# Bending_Machine_SCH.net
KiCad netlist of a schematic drawn in Altium Designer
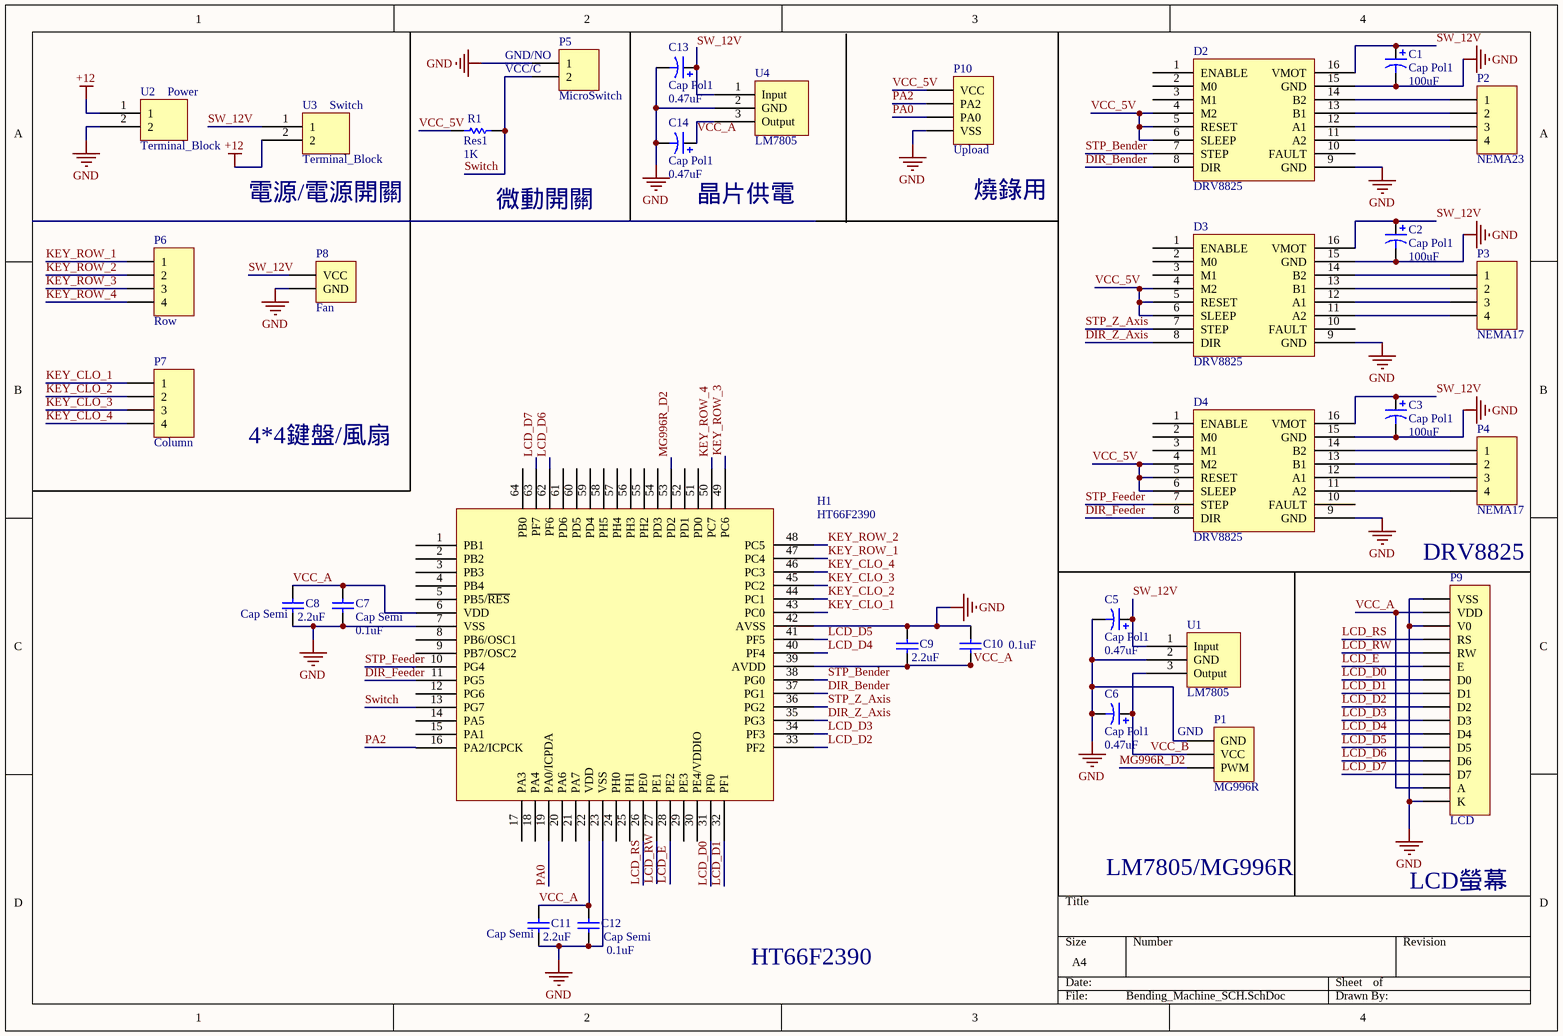
[diagram p0: Bending_Machine_SCH.SchDoc]

(export (version "E")
  (design (tool "Eeschema 10.0.6"))
  (components
    (comp (ref "C1")
      (value "Cap Pol1")
      (footprint "Cap_100uF")
      (description "Polarized Capacitor (Radial)")
      (fields (field (name "ALTIUM_VALUE") "100uF") (field (name "PUBLISHER") "Altium Limited"))
      (libsource (lib "Miscellaneous Devices") (part "Cap Pol1"))
    )
    (comp (ref "C2")
      (value "Cap Pol1")
      (footprint "Cap_100uF")
      (description "Polarized Capacitor (Radial)")
      (fields (field (name "ALTIUM_VALUE") "100uF") (field (name "PUBLISHER") "Altium Limited"))
      (libsource (lib "Miscellaneous Devices") (part "Cap Pol1"))
    )
    (comp (ref "C3")
      (value "Cap Pol1")
      (footprint "Cap_100uF")
      (description "Polarized Capacitor (Radial)")
      (fields (field (name "ALTIUM_VALUE") "100uF") (field (name "PUBLISHER") "Altium Limited"))
      (libsource (lib "Miscellaneous Devices") (part "Cap Pol1"))
    )
    (comp (ref "C5")
      (value "Cap Pol1")
      (footprint "Cap_0.47uF")
      (description "Polarized Capacitor (Radial)")
      (fields (field (name "ALTIUM_VALUE") "0.47uF") (field (name "PUBLISHER") "Altium Limited"))
      (libsource (lib "Miscellaneous Devices") (part "Cap Pol1"))
    )
    (comp (ref "C6")
      (value "Cap Pol1")
      (footprint "Cap_0.47uF")
      (description "Polarized Capacitor (Radial)")
      (fields (field (name "ALTIUM_VALUE") "0.47uF") (field (name "PUBLISHER") "Altium Limited"))
      (libsource (lib "Miscellaneous Devices") (part "Cap Pol1"))
    )
    (comp (ref "C7")
      (value "Cap Semi")
      (footprint "1608[0603]")
      (description "Capacitor (Semiconductor SIM Model)")
      (fields (field (name "ALTIUM_VALUE") "0.1uF") (field (name "PUBLISHER") "Altium Limited"))
      (libsource (lib "Miscellaneous Devices") (part "Cap Semi"))
    )
    (comp (ref "C8")
      (value "Cap Semi")
      (footprint "1608[0603]")
      (description "Capacitor (Semiconductor SIM Model)")
      (fields (field (name "ALTIUM_VALUE") "2.2uF") (field (name "PUBLISHER") "Altium Limited"))
      (libsource (lib "Miscellaneous Devices") (part "Cap Semi"))
    )
    (comp (ref "C9")
      (value "2.2uF")
      (footprint "1608[0603]")
      (description "Capacitor (Semiconductor SIM Model)")
      (fields (field (name "Comment") "Cap Semi") (field (name "PUBLISHER") "Altium Limited"))
      (libsource (lib "Miscellaneous Devices") (part "Cap Semi"))
    )
    (comp (ref "C10")
      (value "0.1uF")
      (footprint "1608[0603]")
      (description "Capacitor (Semiconductor SIM Model)")
      (fields (field (name "Comment") "Cap Semi") (field (name "PUBLISHER") "Altium Limited"))
      (libsource (lib "Miscellaneous Devices") (part "Cap Semi"))
    )
    (comp (ref "C11")
      (value "Cap Semi")
      (footprint "1608[0603]")
      (description "Capacitor (Semiconductor SIM Model)")
      (fields (field (name "ALTIUM_VALUE") "2.2uF") (field (name "PUBLISHER") "Altium Limited"))
      (libsource (lib "Miscellaneous Devices") (part "Cap Semi"))
    )
    (comp (ref "C12")
      (value "Cap Semi")
      (footprint "1608[0603]")
      (description "Capacitor (Semiconductor SIM Model)")
      (fields (field (name "ALTIUM_VALUE") "0.1uF") (field (name "PUBLISHER") "Altium Limited"))
      (libsource (lib "Miscellaneous Devices") (part "Cap Semi"))
    )
    (comp (ref "C13")
      (value "Cap Pol1")
      (footprint "Cap_0.47uF")
      (description "Polarized Capacitor (Radial)")
      (fields (field (name "ALTIUM_VALUE") "0.47uF") (field (name "PUBLISHER") "Altium Limited"))
      (libsource (lib "Miscellaneous Devices") (part "Cap Pol1"))
    )
    (comp (ref "C14")
      (value "Cap Pol1")
      (footprint "Cap_0.47uF")
      (description "Polarized Capacitor (Radial)")
      (fields (field (name "ALTIUM_VALUE") "0.47uF") (field (name "PUBLISHER") "Altium Limited"))
      (libsource (lib "Miscellaneous Devices") (part "Cap Pol1"))
    )
    (comp (ref "D2")
      (value "DRV8825")
      (footprint "DRV8825")
      (libsource (lib "Bending_Machine") (part "DRV8825"))
    )
    (comp (ref "D3")
      (value "DRV8825")
      (footprint "DRV8825")
      (libsource (lib "Bending_Machine") (part "DRV8825"))
    )
    (comp (ref "D4")
      (value "DRV8825")
      (footprint "DRV8825")
      (libsource (lib "Bending_Machine") (part "DRV8825"))
    )
    (comp (ref "H1")
      (value "HT66F2390")
      (footprint "HT66F2390_Bord")
      (libsource (lib "Bending_Machine") (part "HT66F2390"))
    )
    (comp (ref "P1")
      (value "MG996R")
      (footprint "HDR1X3")
      (description "Header, 3-Pin")
      (fields (field (name "PUBLISHER") "Altium Limited"))
      (libsource (lib "Miscellaneous Connectors") (part "Header 3"))
    )
    (comp (ref "P2")
      (value "NEMA23")
      (footprint "HDR1X4")
      (description "Header, 4-Pin")
      (fields (field (name "PUBLISHER") "Altium Limited"))
      (libsource (lib "Miscellaneous Connectors") (part "Header 4"))
    )
    (comp (ref "P3")
      (value "NEMA17")
      (footprint "HDR1X4")
      (description "Header, 4-Pin")
      (fields (field (name "PUBLISHER") "Altium Limited"))
      (libsource (lib "Miscellaneous Connectors") (part "Header 4"))
    )
    (comp (ref "P4")
      (value "NEMA17")
      (footprint "HDR1X4")
      (description "Header, 4-Pin")
      (fields (field (name "PUBLISHER") "Altium Limited"))
      (libsource (lib "Miscellaneous Connectors") (part "Header 4"))
    )
    (comp (ref "P5")
      (value "MicroSwitch")
      (footprint "HDR1X2")
      (description "Header, 2-Pin")
      (fields (field (name "PUBLISHER") "Altium Limited"))
      (libsource (lib "Miscellaneous Connectors") (part "Header 2"))
    )
    (comp (ref "P6")
      (value "Row")
      (footprint "HDR1X4")
      (description "Header, 4-Pin")
      (fields (field (name "PUBLISHER") "Altium Limited"))
      (libsource (lib "Miscellaneous Connectors") (part "Header 4"))
    )
    (comp (ref "P7")
      (value "Column")
      (footprint "HDR1X4")
      (description "Header, 4-Pin")
      (fields (field (name "PUBLISHER") "Altium Limited"))
      (libsource (lib "Miscellaneous Connectors") (part "Header 4"))
    )
    (comp (ref "P8")
      (value "Fan")
      (footprint "HDR1X2")
      (description "Header, 2-Pin")
      (fields (field (name "PUBLISHER") "Altium Limited"))
      (libsource (lib "Miscellaneous Connectors") (part "Header 2"))
    )
    (comp (ref "P9")
      (value "LCD")
      (footprint "HDR1X16")
      (description "Header, 16-Pin")
      (fields (field (name "PUBLISHER") "Altium Limited"))
      (libsource (lib "Miscellaneous Connectors") (part "Header 16"))
    )
    (comp (ref "P10")
      (value "Upload")
      (footprint "HDR1X4")
      (description "Header, 4-Pin")
      (fields (field (name "PUBLISHER") "Altium Limited"))
      (libsource (lib "Miscellaneous Connectors") (part "Header 4"))
    )
    (comp (ref "R1")
      (value "Res1")
      (footprint "AXIAL-0.3")
      (description "Resistor")
      (fields (field (name "ALTIUM_VALUE") "1K") (field (name "PUBLISHER") "Altium Limited"))
      (libsource (lib "Miscellaneous Devices") (part "Res1"))
    )
    (comp (ref "U1")
      (value "LM7805")
      (footprint "LM7805")
      (libsource (lib "Bending_Machine") (part "LM7805"))
    )
    (comp (ref "U2")
      (value "Terminal_Block")
      (footprint "terminal block")
      (libsource (lib "Bending_Machine") (part "Terminal Block"))
    )
    (comp (ref "U3")
      (value "Terminal_Block")
      (footprint "terminal block")
      (libsource (lib "Bending_Machine") (part "Terminal Block"))
    )
    (comp (ref "U4")
      (value "LM7805")
      (footprint "LM7805")
      (libsource (lib "Bending_Machine") (part "LM7805"))
    )
  )
  (nets
    (net (code "1") (name "+12") (class "Default")
      (node (ref "U2") (pin "1") (pinfunction "1_1") (pintype "passive"))
      (node (ref "U3") (pin "2") (pinfunction "2_2") (pintype "passive"))
    )
    (net (code "3") (name "/DIR_Bender") (class "Default")
      (node (ref "D2") (pin "8") (pinfunction "DIR_8") (pintype "passive"))
      (node (ref "H1") (pin "37") (pinfunction "PG1_37") (pintype "passive"))
    )
    (net (code "4") (name "/DIR_Feeder") (class "Default")
      (node (ref "D4") (pin "8") (pinfunction "DIR_8") (pintype "passive"))
      (node (ref "H1") (pin "11") (pinfunction "PG5_11") (pintype "passive"))
    )
    (net (code "5") (name "/DIR_Z_Axis") (class "Default")
      (node (ref "D3") (pin "8") (pinfunction "DIR_8") (pintype "passive"))
      (node (ref "H1") (pin "35") (pinfunction "PG3_35") (pintype "passive"))
    )
    (net (code "6") (name "/KEY_CLO_1") (class "Default")
      (node (ref "H1") (pin "43") (pinfunction "PC0_43") (pintype "passive"))
      (node (ref "P7") (pin "1") (pinfunction "1_1") (pintype "passive"))
    )
    (net (code "7") (name "/KEY_CLO_2") (class "Default")
      (node (ref "H1") (pin "44") (pinfunction "PC1_44") (pintype "passive"))
      (node (ref "P7") (pin "2") (pinfunction "2_2") (pintype "passive"))
    )
    (net (code "8") (name "/KEY_CLO_3") (class "Default")
      (node (ref "H1") (pin "45") (pinfunction "PC2_45") (pintype "passive"))
      (node (ref "P7") (pin "3") (pinfunction "3_3") (pintype "passive"))
    )
    (net (code "9") (name "/KEY_CLO_4") (class "Default")
      (node (ref "H1") (pin "46") (pinfunction "PC3_46") (pintype "passive"))
      (node (ref "P7") (pin "4") (pinfunction "4_4") (pintype "passive"))
    )
    (net (code "10") (name "/KEY_ROW_1") (class "Default")
      (node (ref "H1") (pin "47") (pinfunction "PC4_47") (pintype "passive"))
      (node (ref "P6") (pin "1") (pinfunction "1_1") (pintype "passive"))
    )
    (net (code "11") (name "/KEY_ROW_2") (class "Default")
      (node (ref "H1") (pin "48") (pinfunction "PC5_48") (pintype "passive"))
      (node (ref "P6") (pin "2") (pinfunction "2_2") (pintype "passive"))
    )
    (net (code "12") (name "/KEY_ROW_3") (class "Default")
      (node (ref "H1") (pin "49") (pinfunction "PC6_49") (pintype "passive"))
      (node (ref "P6") (pin "3") (pinfunction "3_3") (pintype "passive"))
    )
    (net (code "13") (name "/KEY_ROW_4") (class "Default")
      (node (ref "H1") (pin "50") (pinfunction "PC7_50") (pintype "passive"))
      (node (ref "P6") (pin "4") (pinfunction "4_4") (pintype "passive"))
    )
    (net (code "14") (name "/LCD_D0") (class "Default")
      (node (ref "H1") (pin "31") (pinfunction "PF0_31") (pintype "passive"))
      (node (ref "P9") (pin "7") (pinfunction "D0_7") (pintype "passive"))
    )
    (net (code "15") (name "/LCD_D1") (class "Default")
      (node (ref "H1") (pin "32") (pinfunction "PF1_32") (pintype "passive"))
      (node (ref "P9") (pin "8") (pinfunction "D1_8") (pintype "passive"))
    )
    (net (code "16") (name "/LCD_D2") (class "Default")
      (node (ref "H1") (pin "33") (pinfunction "PF2_33") (pintype "passive"))
      (node (ref "P9") (pin "9") (pinfunction "D2_9") (pintype "passive"))
    )
    (net (code "17") (name "/LCD_D3") (class "Default")
      (node (ref "H1") (pin "34") (pinfunction "PF3_34") (pintype "passive"))
      (node (ref "P9") (pin "10") (pinfunction "D3_10") (pintype "passive"))
    )
    (net (code "18") (name "/LCD_D4") (class "Default")
      (node (ref "H1") (pin "40") (pinfunction "PF4_40") (pintype "passive"))
      (node (ref "P9") (pin "11") (pinfunction "D4_11") (pintype "passive"))
    )
    (net (code "19") (name "/LCD_D5") (class "Default")
      (node (ref "H1") (pin "41") (pinfunction "PF5_41") (pintype "passive"))
      (node (ref "P9") (pin "12") (pinfunction "D5_12") (pintype "passive"))
    )
    (net (code "20") (name "/LCD_D6") (class "Default")
      (node (ref "H1") (pin "62") (pinfunction "PF6_62") (pintype "passive"))
      (node (ref "P9") (pin "13") (pinfunction "D6_13") (pintype "passive"))
    )
    (net (code "21") (name "/LCD_D7") (class "Default")
      (node (ref "H1") (pin "63") (pinfunction "PF7_63") (pintype "passive"))
      (node (ref "P9") (pin "14") (pinfunction "D7_14") (pintype "passive"))
    )
    (net (code "22") (name "/LCD_E") (class "Default")
      (node (ref "H1") (pin "28") (pinfunction "PE2_28") (pintype "passive"))
      (node (ref "P9") (pin "6") (pinfunction "E_6") (pintype "passive"))
    )
    (net (code "23") (name "/LCD_RS") (class "Default")
      (node (ref "H1") (pin "26") (pinfunction "PE0_26") (pintype "passive"))
      (node (ref "P9") (pin "4") (pinfunction "RS_4") (pintype "passive"))
    )
    (net (code "24") (name "/LCD_RW") (class "Default")
      (node (ref "H1") (pin "27") (pinfunction "PE1_27") (pintype "passive"))
      (node (ref "P9") (pin "5") (pinfunction "RW_5") (pintype "passive"))
    )
    (net (code "25") (name "/MG996R_D2") (class "Default")
      (node (ref "H1") (pin "53") (pinfunction "PD2_53") (pintype "passive"))
      (node (ref "P1") (pin "3") (pinfunction "PWM_3") (pintype "passive"))
    )
    (net (code "26") (name "/PA0") (class "Default")
      (node (ref "H1") (pin "19") (pinfunction "PA0/ICPDA_19") (pintype "passive"))
      (node (ref "P10") (pin "3") (pinfunction "3_3") (pintype "passive"))
    )
    (net (code "27") (name "/PA2") (class "Default")
      (node (ref "H1") (pin "16") (pinfunction "PA2/ICPCK_16") (pintype "passive"))
      (node (ref "P10") (pin "2") (pinfunction "2_2") (pintype "passive"))
    )
    (net (code "28") (name "/STP_Bender") (class "Default")
      (node (ref "D2") (pin "7") (pinfunction "STEP_7") (pintype "passive"))
      (node (ref "H1") (pin "38") (pinfunction "PG0_38") (pintype "passive"))
    )
    (net (code "29") (name "/STP_Feeder") (class "Default")
      (node (ref "D4") (pin "7") (pinfunction "STEP_7") (pintype "passive"))
      (node (ref "H1") (pin "10") (pinfunction "PG4_10") (pintype "passive"))
    )
    (net (code "30") (name "/STP_Z_Axis") (class "Default")
      (node (ref "D3") (pin "7") (pinfunction "STEP_7") (pintype "passive"))
      (node (ref "H1") (pin "36") (pinfunction "PG2_36") (pintype "passive"))
    )
    (net (code "31") (name "/SW_12V") (class "Default")
      (node (ref "C1") (pin "1") (pinfunction "1_1") (pintype "passive"))
      (node (ref "C13") (pin "1") (pinfunction "1_1") (pintype "passive"))
      (node (ref "C2") (pin "1") (pinfunction "1_1") (pintype "passive"))
      (node (ref "C3") (pin "1") (pinfunction "1_1") (pintype "passive"))
      (node (ref "C5") (pin "1") (pinfunction "1_1") (pintype "passive"))
      (node (ref "D2") (pin "16") (pinfunction "VMOT_16") (pintype "passive"))
      (node (ref "D3") (pin "16") (pinfunction "VMOT_16") (pintype "passive"))
      (node (ref "D4") (pin "16") (pinfunction "VMOT_16") (pintype "passive"))
      (node (ref "P8") (pin "1") (pinfunction "1_1") (pintype "passive"))
      (node (ref "U1") (pin "1") (pinfunction "Input_1") (pintype "passive"))
      (node (ref "U3") (pin "1") (pinfunction "1_1") (pintype "passive"))
      (node (ref "U4") (pin "1") (pinfunction "Input_1") (pintype "passive"))
    )
    (net (code "32") (name "/Switch") (class "Default")
      (node (ref "H1") (pin "13") (pinfunction "PG7_13") (pintype "passive"))
      (node (ref "P5") (pin "2") (pinfunction "2_2") (pintype "passive"))
      (node (ref "R1") (pin "2") (pinfunction "2_2") (pintype "passive"))
    )
    (net (code "33") (name "/VCC_5V") (class "Default")
      (node (ref "D2") (pin "4") (pinfunction "M2_4") (pintype "passive"))
      (node (ref "D2") (pin "5") (pinfunction "RESET_5") (pintype "passive"))
      (node (ref "D2") (pin "6") (pinfunction "SLEEP_6") (pintype "passive"))
      (node (ref "D3") (pin "4") (pinfunction "M2_4") (pintype "passive"))
      (node (ref "D3") (pin "5") (pinfunction "RESET_5") (pintype "passive"))
      (node (ref "D3") (pin "6") (pinfunction "SLEEP_6") (pintype "passive"))
      (node (ref "D4") (pin "4") (pinfunction "M2_4") (pintype "passive"))
      (node (ref "D4") (pin "5") (pinfunction "RESET_5") (pintype "passive"))
      (node (ref "D4") (pin "6") (pinfunction "SLEEP_6") (pintype "passive"))
      (node (ref "P10") (pin "1") (pinfunction "1_1") (pintype "passive"))
      (node (ref "R1") (pin "1") (pinfunction "1_1") (pintype "passive"))
    )
    (net (code "34") (name "/VCC_A") (class "Default")
      (node (ref "C10") (pin "1") (pinfunction "1_1") (pintype "passive"))
      (node (ref "C11") (pin "2") (pinfunction "2_2") (pintype "passive"))
      (node (ref "C12") (pin "2") (pinfunction "2_2") (pintype "passive"))
      (node (ref "C14") (pin "1") (pinfunction "1_1") (pintype "passive"))
      (node (ref "C7") (pin "2") (pinfunction "2_2") (pintype "passive"))
      (node (ref "C8") (pin "2") (pinfunction "2_2") (pintype "passive"))
      (node (ref "C9") (pin "1") (pinfunction "1_1") (pintype "passive"))
      (node (ref "H1") (pin "22") (pinfunction "VDD_22") (pintype "passive"))
      (node (ref "H1") (pin "39") (pinfunction "AVDD_39") (pintype "passive"))
      (node (ref "H1") (pin "6") (pinfunction "VDD_6") (pintype "passive"))
      (node (ref "P9") (pin "15") (pinfunction "A_15") (pintype "passive"))
      (node (ref "P9") (pin "2") (pinfunction "VDD_2") (pintype "passive"))
      (node (ref "U4") (pin "3") (pinfunction "Output_3") (pintype "passive"))
    )
    (net (code "35") (name "/VCC_B") (class "Default")
      (node (ref "C6") (pin "1") (pinfunction "1_1") (pintype "passive"))
      (node (ref "P1") (pin "2") (pinfunction "VCC_2") (pintype "passive"))
      (node (ref "U1") (pin "3") (pinfunction "Output_3") (pintype "passive"))
    )
    (net (code "36") (name "GND") (class "Default")
      (node (ref "C1") (pin "2") (pinfunction "2_2") (pintype "passive"))
      (node (ref "C10") (pin "2") (pinfunction "2_2") (pintype "passive"))
      (node (ref "C11") (pin "1") (pinfunction "1_1") (pintype "passive"))
      (node (ref "C12") (pin "1") (pinfunction "1_1") (pintype "passive"))
      (node (ref "C13") (pin "2") (pinfunction "2_2") (pintype "passive"))
      (node (ref "C14") (pin "2") (pinfunction "2_2") (pintype "passive"))
      (node (ref "C2") (pin "2") (pinfunction "2_2") (pintype "passive"))
      (node (ref "C3") (pin "2") (pinfunction "2_2") (pintype "passive"))
      (node (ref "C5") (pin "2") (pinfunction "2_2") (pintype "passive"))
      (node (ref "C6") (pin "2") (pinfunction "2_2") (pintype "passive"))
      (node (ref "C7") (pin "1") (pinfunction "1_1") (pintype "passive"))
      (node (ref "C8") (pin "1") (pinfunction "1_1") (pintype "passive"))
      (node (ref "C9") (pin "2") (pinfunction "2_2") (pintype "passive"))
      (node (ref "D2") (pin "15") (pinfunction "GND_15") (pintype "passive"))
      (node (ref "D2") (pin "9") (pinfunction "GND_9") (pintype "passive"))
      (node (ref "D3") (pin "15") (pinfunction "GND_15") (pintype "passive"))
      (node (ref "D3") (pin "9") (pinfunction "GND_9") (pintype "passive"))
      (node (ref "D4") (pin "15") (pinfunction "GND_15") (pintype "passive"))
      (node (ref "D4") (pin "9") (pinfunction "GND_9") (pintype "passive"))
      (node (ref "H1") (pin "23") (pinfunction "VSS_23") (pintype "passive"))
      (node (ref "H1") (pin "42") (pinfunction "AVSS_42") (pintype "passive"))
      (node (ref "H1") (pin "7") (pinfunction "VSS_7") (pintype "passive"))
      (node (ref "P1") (pin "1") (pinfunction "GND_1") (pintype "passive"))
      (node (ref "P10") (pin "4") (pinfunction "4_4") (pintype "passive"))
      (node (ref "P5") (pin "1") (pinfunction "1_1") (pintype "passive"))
      (node (ref "P8") (pin "2") (pinfunction "2_2") (pintype "passive"))
      (node (ref "P9") (pin "1") (pinfunction "VSS_1") (pintype "passive"))
      (node (ref "P9") (pin "16") (pinfunction "K_16") (pintype "passive"))
      (node (ref "P9") (pin "3") (pinfunction "V0_3") (pintype "passive"))
      (node (ref "U1") (pin "2") (pinfunction "GND_2") (pintype "passive"))
      (node (ref "U2") (pin "2") (pinfunction "2_2") (pintype "passive"))
      (node (ref "U4") (pin "2") (pinfunction "GND_2") (pintype "passive"))
    )
    (net (code "37") (name "Net-(D2-A1)") (class "Default")
      (node (ref "D2") (pin "12") (pinfunction "A1_12") (pintype "passive"))
      (node (ref "P2") (pin "3") (pinfunction "3_3") (pintype "passive"))
    )
    (net (code "38") (name "Net-(D2-A2)") (class "Default")
      (node (ref "D2") (pin "11") (pinfunction "A2_11") (pintype "passive"))
      (node (ref "P2") (pin "4") (pinfunction "4_4") (pintype "passive"))
    )
    (net (code "39") (name "Net-(D2-B1)") (class "Default")
      (node (ref "D2") (pin "13") (pinfunction "B1_13") (pintype "passive"))
      (node (ref "P2") (pin "2") (pinfunction "2_2") (pintype "passive"))
    )
    (net (code "40") (name "Net-(D2-B2)") (class "Default")
      (node (ref "D2") (pin "14") (pinfunction "B2_14") (pintype "passive"))
      (node (ref "P2") (pin "1") (pinfunction "1_1") (pintype "passive"))
    )
    (net (code "41") (name "Net-(D3-A1)") (class "Default")
      (node (ref "D3") (pin "12") (pinfunction "A1_12") (pintype "passive"))
      (node (ref "P3") (pin "3") (pinfunction "3_3") (pintype "passive"))
    )
    (net (code "42") (name "Net-(D3-A2)") (class "Default")
      (node (ref "D3") (pin "11") (pinfunction "A2_11") (pintype "passive"))
      (node (ref "P3") (pin "4") (pinfunction "4_4") (pintype "passive"))
    )
    (net (code "43") (name "Net-(D3-B1)") (class "Default")
      (node (ref "D3") (pin "13") (pinfunction "B1_13") (pintype "passive"))
      (node (ref "P3") (pin "2") (pinfunction "2_2") (pintype "passive"))
    )
    (net (code "44") (name "Net-(D3-B2)") (class "Default")
      (node (ref "D3") (pin "14") (pinfunction "B2_14") (pintype "passive"))
      (node (ref "P3") (pin "1") (pinfunction "1_1") (pintype "passive"))
    )
    (net (code "45") (name "Net-(D4-A1)") (class "Default")
      (node (ref "D4") (pin "12") (pinfunction "A1_12") (pintype "passive"))
      (node (ref "P4") (pin "3") (pinfunction "3_3") (pintype "passive"))
    )
    (net (code "46") (name "Net-(D4-A2)") (class "Default")
      (node (ref "D4") (pin "11") (pinfunction "A2_11") (pintype "passive"))
      (node (ref "P4") (pin "4") (pinfunction "4_4") (pintype "passive"))
    )
    (net (code "47") (name "Net-(D4-B1)") (class "Default")
      (node (ref "D4") (pin "13") (pinfunction "B1_13") (pintype "passive"))
      (node (ref "P4") (pin "2") (pinfunction "2_2") (pintype "passive"))
    )
    (net (code "48") (name "Net-(D4-B2)") (class "Default")
      (node (ref "D4") (pin "14") (pinfunction "B2_14") (pintype "passive"))
      (node (ref "P4") (pin "1") (pinfunction "1_1") (pintype "passive"))
    )
    (net (code "49") (name "unconnected-(D2-ENABLE-Pad1)") (class "Default")
      (node (ref "D2") (pin "1") (pinfunction "ENABLE_1") (pintype "passive"))
    )
    (net (code "50") (name "unconnected-(D2-FAULT-Pad10)") (class "Default")
      (node (ref "D2") (pin "10") (pinfunction "FAULT_10") (pintype "passive"))
    )
    (net (code "51") (name "unconnected-(D2-M0-Pad2)") (class "Default")
      (node (ref "D2") (pin "2") (pinfunction "M0_2") (pintype "passive"))
    )
    (net (code "52") (name "unconnected-(D2-M1-Pad3)") (class "Default")
      (node (ref "D2") (pin "3") (pinfunction "M1_3") (pintype "passive"))
    )
    (net (code "53") (name "unconnected-(D3-ENABLE-Pad1)") (class "Default")
      (node (ref "D3") (pin "1") (pinfunction "ENABLE_1") (pintype "passive"))
    )
    (net (code "54") (name "unconnected-(D3-FAULT-Pad10)") (class "Default")
      (node (ref "D3") (pin "10") (pinfunction "FAULT_10") (pintype "passive"))
    )
    (net (code "55") (name "unconnected-(D3-M0-Pad2)") (class "Default")
      (node (ref "D3") (pin "2") (pinfunction "M0_2") (pintype "passive"))
    )
    (net (code "56") (name "unconnected-(D3-M1-Pad3)") (class "Default")
      (node (ref "D3") (pin "3") (pinfunction "M1_3") (pintype "passive"))
    )
    (net (code "57") (name "unconnected-(D4-ENABLE-Pad1)") (class "Default")
      (node (ref "D4") (pin "1") (pinfunction "ENABLE_1") (pintype "passive"))
    )
    (net (code "58") (name "unconnected-(D4-FAULT-Pad10)") (class "Default")
      (node (ref "D4") (pin "10") (pinfunction "FAULT_10") (pintype "passive"))
    )
    (net (code "59") (name "unconnected-(D4-M0-Pad2)") (class "Default")
      (node (ref "D4") (pin "2") (pinfunction "M0_2") (pintype "passive"))
    )
    (net (code "60") (name "unconnected-(D4-M1-Pad3)") (class "Default")
      (node (ref "D4") (pin "3") (pinfunction "M1_3") (pintype "passive"))
    )
    (net (code "61") (name "unconnected-(H1-PA1-Pad15)") (class "Default")
      (node (ref "H1") (pin "15") (pinfunction "PA1_15") (pintype "passive"))
    )
    (net (code "62") (name "unconnected-(H1-PA3-Pad17)") (class "Default")
      (node (ref "H1") (pin "17") (pinfunction "PA3_17") (pintype "passive"))
    )
    (net (code "63") (name "unconnected-(H1-PA4-Pad18)") (class "Default")
      (node (ref "H1") (pin "18") (pinfunction "PA4_18") (pintype "passive"))
    )
    (net (code "64") (name "unconnected-(H1-PA5-Pad14)") (class "Default")
      (node (ref "H1") (pin "14") (pinfunction "PA5_14") (pintype "passive"))
    )
    (net (code "65") (name "unconnected-(H1-PA6-Pad20)") (class "Default")
      (node (ref "H1") (pin "20") (pinfunction "PA6_20") (pintype "passive"))
    )
    (net (code "66") (name "unconnected-(H1-PA7-Pad21)") (class "Default")
      (node (ref "H1") (pin "21") (pinfunction "PA7_21") (pintype "passive"))
    )
    (net (code "67") (name "unconnected-(H1-PB0-Pad64)") (class "Default")
      (node (ref "H1") (pin "64") (pinfunction "PB0_64") (pintype "passive"))
    )
    (net (code "68") (name "unconnected-(H1-PB1-Pad1)") (class "Default")
      (node (ref "H1") (pin "1") (pinfunction "PB1_1") (pintype "passive"))
    )
    (net (code "69") (name "unconnected-(H1-PB2-Pad2)") (class "Default")
      (node (ref "H1") (pin "2") (pinfunction "PB2_2") (pintype "passive"))
    )
    (net (code "70") (name "unconnected-(H1-PB3-Pad3)") (class "Default")
      (node (ref "H1") (pin "3") (pinfunction "PB3_3") (pintype "passive"))
    )
    (net (code "71") (name "unconnected-(H1-PB4-Pad4)") (class "Default")
      (node (ref "H1") (pin "4") (pinfunction "PB4_4") (pintype "passive"))
    )
    (net (code "72") (name "unconnected-(H1-PB5{slash}~{RES}-Pad5)") (class "Default")
      (node (ref "H1") (pin "5") (pinfunction "PB5/~{RES}_5") (pintype "passive"))
    )
    (net (code "73") (name "unconnected-(H1-PB6{slash}OSC1-Pad8)") (class "Default")
      (node (ref "H1") (pin "8") (pinfunction "PB6/OSC1_8") (pintype "passive"))
    )
    (net (code "74") (name "unconnected-(H1-PB7{slash}OSC2-Pad9)") (class "Default")
      (node (ref "H1") (pin "9") (pinfunction "PB7/OSC2_9") (pintype "passive"))
    )
    (net (code "75") (name "unconnected-(H1-PD0-Pad51)") (class "Default")
      (node (ref "H1") (pin "51") (pinfunction "PD0_51") (pintype "passive"))
    )
    (net (code "76") (name "unconnected-(H1-PD1-Pad52)") (class "Default")
      (node (ref "H1") (pin "52") (pinfunction "PD1_52") (pintype "passive"))
    )
    (net (code "77") (name "unconnected-(H1-PD3-Pad54)") (class "Default")
      (node (ref "H1") (pin "54") (pinfunction "PD3_54") (pintype "passive"))
    )
    (net (code "78") (name "unconnected-(H1-PD4-Pad59)") (class "Default")
      (node (ref "H1") (pin "59") (pinfunction "PD4_59") (pintype "passive"))
    )
    (net (code "79") (name "unconnected-(H1-PD5-Pad60)") (class "Default")
      (node (ref "H1") (pin "60") (pinfunction "PD5_60") (pintype "passive"))
    )
    (net (code "80") (name "unconnected-(H1-PD6-Pad61)") (class "Default")
      (node (ref "H1") (pin "61") (pinfunction "PD6_61") (pintype "passive"))
    )
    (net (code "81") (name "unconnected-(H1-PE3-Pad29)") (class "Default")
      (node (ref "H1") (pin "29") (pinfunction "PE3_29") (pintype "passive"))
    )
    (net (code "82") (name "unconnected-(H1-PE4{slash}VDDIO-Pad30)") (class "Default")
      (node (ref "H1") (pin "30") (pinfunction "PE4/VDDIO_30") (pintype "passive"))
    )
    (net (code "83") (name "unconnected-(H1-PG6-Pad12)") (class "Default")
      (node (ref "H1") (pin "12") (pinfunction "PG6_12") (pintype "passive"))
    )
    (net (code "84") (name "unconnected-(H1-PH0-Pad24)") (class "Default")
      (node (ref "H1") (pin "24") (pinfunction "PH0_24") (pintype "passive"))
    )
    (net (code "85") (name "unconnected-(H1-PH1-Pad25)") (class "Default")
      (node (ref "H1") (pin "25") (pinfunction "PH1_25") (pintype "passive"))
    )
    (net (code "86") (name "unconnected-(H1-PH2-Pad55)") (class "Default")
      (node (ref "H1") (pin "55") (pinfunction "PH2_55") (pintype "passive"))
    )
    (net (code "87") (name "unconnected-(H1-PH3-Pad56)") (class "Default")
      (node (ref "H1") (pin "56") (pinfunction "PH3_56") (pintype "passive"))
    )
    (net (code "88") (name "unconnected-(H1-PH4-Pad57)") (class "Default")
      (node (ref "H1") (pin "57") (pinfunction "PH4_57") (pintype "passive"))
    )
    (net (code "89") (name "unconnected-(H1-PH5-Pad58)") (class "Default")
      (node (ref "H1") (pin "58") (pinfunction "PH5_58") (pintype "passive"))
    )
  )
)
